# 02_GAP9_CHIP_POWER.net
KiCad netlist of a schematic drawn in Altium Designer
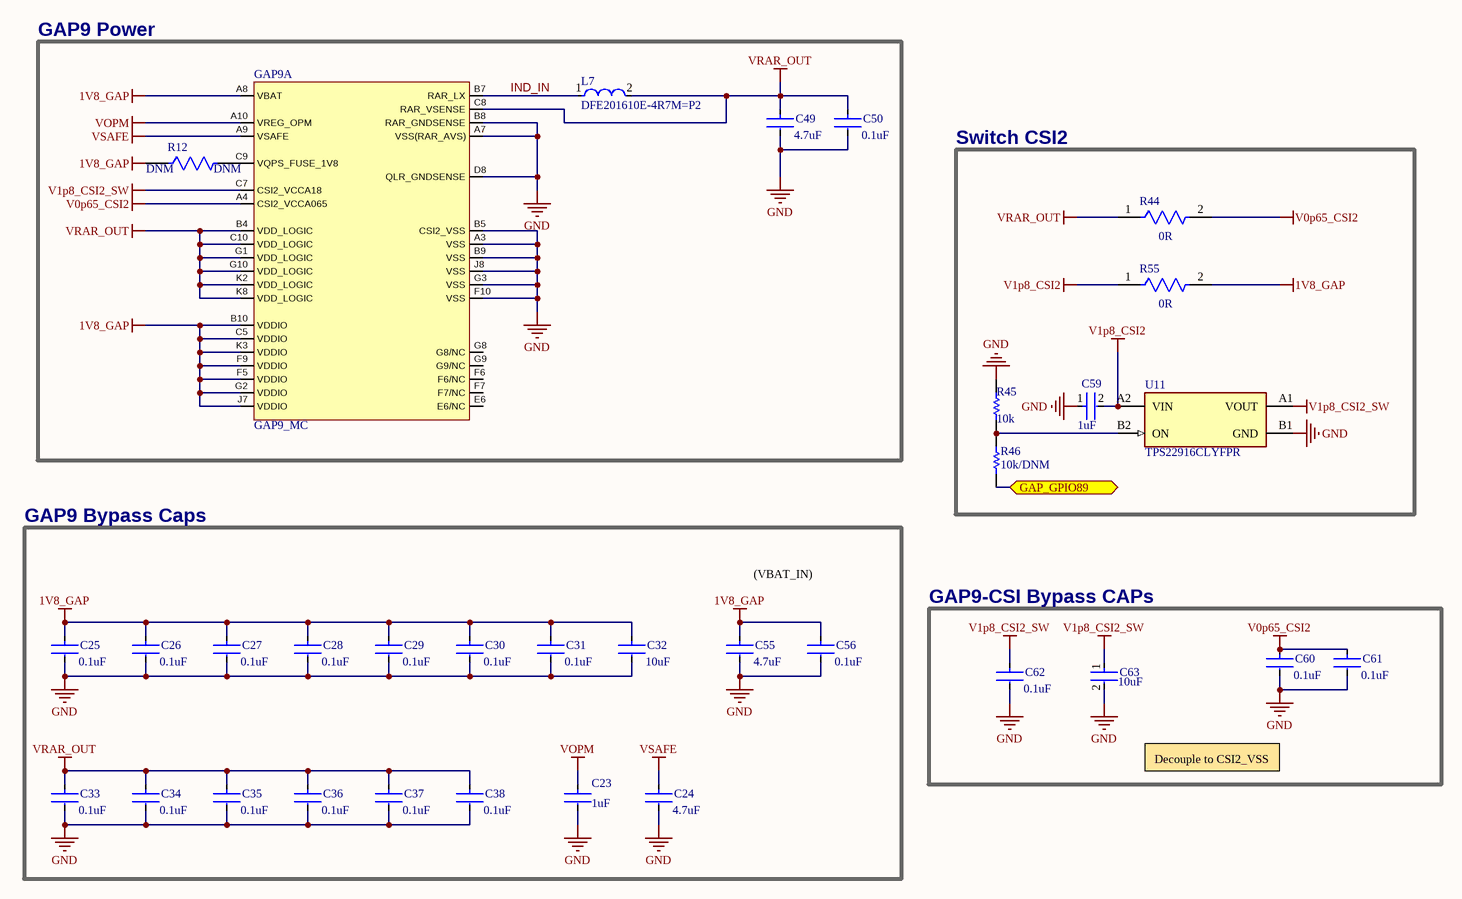
[diagram p0: 02_GAP9_CHIP_POWER.SchDoc]

(export (version "E")
  (design (tool "Eeschema 10.0.6"))
  (components
    (comp (ref "C23")
      (value "CL03A105KP3NSNC")
      (footprint "FP-CL03-IPC_B")
      (description "Cap Ceramic 1uF 10V X5R ±10% Pad SMD 0201 +85°C T/R")
      (fields (field (name "TOLERANCE") "10%") (field (name "CAPACITANCE") "1uF"))
      (libsource (lib "Altium Content Vault") (part "b4654b650e69147ec39a6b967a45e02"))
    )
    (comp (ref "C24")
      (value "C1005X5R0J475K050BC")
      (footprint "FP-C1005-050-0_15-IPC_B")
      (description "Chip Multilayer Ceramic Capacitors for General Purpose, 0402, 4.7uF")
      (fields
        (field (name "VOLTAGE") "6.3V")
        (field (name "CAPACITANCE") "4.7uF")
        (field (name "TOLERANCE") "10%")
      )
      (libsource (lib "Altium Content Vault") (part "02cd4be3c70576c341d710602a673aa"))
    )
    (comp (ref "C25")
      (value "GRM033Z71C104KE14D")
      (footprint "FP-GRM033-0_03-IPC_B")
      (description "Chip Multilayer Ceramic Capacitors for General Purpose, 0201, 0.10uF, X7R, 15%, 10%, 16V")
      (fields (field (name "CAPACITANCE") "0.1uF"))
      (libsource (lib "Altium Content Vault") (part "b4654b650e69147ec39a6b967a45e02"))
    )
    (comp (ref "C26")
      (value "GRM033Z71C104KE14D")
      (footprint "FP-GRM033-0_03-IPC_B")
      (description "Chip Multilayer Ceramic Capacitors for General Purpose, 0201, 0.10uF, X7R, 15%, 10%, 16V")
      (fields (field (name "CAPACITANCE") "0.1uF"))
      (libsource (lib "Altium Content Vault") (part "b4654b650e69147ec39a6b967a45e02"))
    )
    (comp (ref "C27")
      (value "GRM033Z71C104KE14D")
      (footprint "FP-GRM033-0_03-IPC_B")
      (description "Chip Multilayer Ceramic Capacitors for General Purpose, 0201, 0.10uF, X7R, 15%, 10%, 16V")
      (fields (field (name "CAPACITANCE") "0.1uF"))
      (libsource (lib "Altium Content Vault") (part "b4654b650e69147ec39a6b967a45e02"))
    )
    (comp (ref "C28")
      (value "GRM033Z71C104KE14D")
      (footprint "FP-GRM033-0_03-IPC_B")
      (description "Chip Multilayer Ceramic Capacitors for General Purpose, 0201, 0.10uF, X7R, 15%, 10%, 16V")
      (fields (field (name "CAPACITANCE") "0.1uF"))
      (libsource (lib "Altium Content Vault") (part "b4654b650e69147ec39a6b967a45e02"))
    )
    (comp (ref "C29")
      (value "GRM033Z71C104KE14D")
      (footprint "FP-GRM033-0_03-IPC_B")
      (description "Chip Multilayer Ceramic Capacitors for General Purpose, 0201, 0.10uF, X7R, 15%, 10%, 16V")
      (fields (field (name "CAPACITANCE") "0.1uF"))
      (libsource (lib "Altium Content Vault") (part "b4654b650e69147ec39a6b967a45e02"))
    )
    (comp (ref "C30")
      (value "GRM033Z71C104KE14D")
      (footprint "FP-GRM033-0_03-IPC_B")
      (description "Chip Multilayer Ceramic Capacitors for General Purpose, 0201, 0.10uF, X7R, 15%, 10%, 16V")
      (fields (field (name "CAPACITANCE") "0.1uF"))
      (libsource (lib "Altium Content Vault") (part "b4654b650e69147ec39a6b967a45e02"))
    )
    (comp (ref "C31")
      (value "GRM033Z71C104KE14D")
      (footprint "FP-GRM033-0_03-IPC_B")
      (description "Chip Multilayer Ceramic Capacitors for General Purpose, 0201, 0.10uF, X7R, 15%, 10%, 16V")
      (fields (field (name "CAPACITANCE") "0.1uF"))
      (libsource (lib "Altium Content Vault") (part "b4654b650e69147ec39a6b967a45e02"))
    )
    (comp (ref "C32")
      (value "CL05A106MP5NUNC")
      (footprint "FP-CL05A106MP5NUNC-IPC_B")
      (description "CAP CER 10UF 10V X5R 0402")
      (fields
        (field (name "OCTOPART") "https://octopart.com/cl05a106mp5nunc-samsung-22457395")
        (field (name "TOLERANCE") "20%")
        (field (name "CAPACITANCE") "10uF")
      )
      (libsource (lib "Altium Content Vault") (part "b4654b650e69147ec39a6b967a45e02"))
    )
    (comp (ref "C33")
      (value "GRM033Z71C104KE14D")
      (footprint "FP-GRM033-0_03-IPC_B")
      (description "Chip Multilayer Ceramic Capacitors for General Purpose, 0201, 0.10uF, X7R, 15%, 10%, 16V")
      (fields (field (name "CAPACITANCE") "0.1uF"))
      (libsource (lib "Altium Content Vault") (part "b4654b650e69147ec39a6b967a45e02"))
    )
    (comp (ref "C34")
      (value "GRM033Z71C104KE14D")
      (footprint "FP-GRM033-0_03-IPC_B")
      (description "Chip Multilayer Ceramic Capacitors for General Purpose, 0201, 0.10uF, X7R, 15%, 10%, 16V")
      (fields (field (name "CAPACITANCE") "0.1uF"))
      (libsource (lib "Altium Content Vault") (part "b4654b650e69147ec39a6b967a45e02"))
    )
    (comp (ref "C35")
      (value "GRM033Z71C104KE14D")
      (footprint "FP-GRM033-0_03-IPC_B")
      (description "Chip Multilayer Ceramic Capacitors for General Purpose, 0201, 0.10uF, X7R, 15%, 10%, 16V")
      (fields (field (name "CAPACITANCE") "0.1uF"))
      (libsource (lib "Altium Content Vault") (part "b4654b650e69147ec39a6b967a45e02"))
    )
    (comp (ref "C36")
      (value "GRM033Z71C104KE14D")
      (footprint "FP-GRM033-0_03-IPC_B")
      (description "Chip Multilayer Ceramic Capacitors for General Purpose, 0201, 0.10uF, X7R, 15%, 10%, 16V")
      (fields (field (name "CAPACITANCE") "0.1uF"))
      (libsource (lib "Altium Content Vault") (part "b4654b650e69147ec39a6b967a45e02"))
    )
    (comp (ref "C37")
      (value "GRM033Z71C104KE14D")
      (footprint "FP-GRM033-0_03-IPC_B")
      (description "Chip Multilayer Ceramic Capacitors for General Purpose, 0201, 0.10uF, X7R, 15%, 10%, 16V")
      (fields (field (name "CAPACITANCE") "0.1uF"))
      (libsource (lib "Altium Content Vault") (part "b4654b650e69147ec39a6b967a45e02"))
    )
    (comp (ref "C38")
      (value "GRM033Z71C104KE14D")
      (footprint "FP-GRM033-0_03-IPC_B")
      (description "Chip Multilayer Ceramic Capacitors for General Purpose, 0201, 0.10uF, X7R, 15%, 10%, 16V")
      (fields (field (name "CAPACITANCE") "0.1uF"))
      (libsource (lib "Altium Content Vault") (part "b4654b650e69147ec39a6b967a45e02"))
    )
    (comp (ref "C49")
      (value "C1005X5R0J475K050BC")
      (footprint "FP-C1005-050-0_15-IPC_B")
      (description "Chip Multilayer Ceramic Capacitors for General Purpose, 0402, 4.7uF")
      (fields
        (field (name "VOLTAGE") "6.3V")
        (field (name "CAPACITANCE") "4.7uF")
        (field (name "TOLERANCE") "10%")
      )
      (libsource (lib "Altium Content Vault") (part "02cd4be3c70576c341d710602a673aa"))
    )
    (comp (ref "C50")
      (value "GRM033Z71C104KE14D")
      (footprint "FP-GRM033-0_03-IPC_B")
      (description "Chip Multilayer Ceramic Capacitors for General Purpose, 0201, 0.10uF, X7R, 15%, 10%, 16V")
      (fields (field (name "CAPACITANCE") "0.1uF"))
      (libsource (lib "Altium Content Vault") (part "b4654b650e69147ec39a6b967a45e02"))
    )
    (comp (ref "C55")
      (value "C1005X5R0J475K050BC")
      (footprint "FP-C1005-050-0_15-IPC_B")
      (description "Chip Multilayer Ceramic Capacitors for General Purpose, 0402, 4.7uF")
      (fields
        (field (name "VOLTAGE") "6.3V")
        (field (name "CAPACITANCE") "4.7uF")
        (field (name "TOLERANCE") "10%")
      )
      (libsource (lib "Altium Content Vault") (part "02cd4be3c70576c341d710602a673aa"))
    )
    (comp (ref "C56")
      (value "GRM033Z71C104KE14D")
      (footprint "FP-GRM033-0_03-IPC_B")
      (description "Chip Multilayer Ceramic Capacitors for General Purpose, 0201, 0.10uF, X7R, 15%, 10%, 16V")
      (fields (field (name "CAPACITANCE") "0.1uF"))
      (libsource (lib "Altium Content Vault") (part "b4654b650e69147ec39a6b967a45e02"))
    )
    (comp (ref "C59")
      (value "1uF")
      (footprint "FP-GRM033-0_09-IPC_C")
      (description "Chip Multilayer Ceramic Capacitors for General Purpose, 0201, 1.0uF, X6S, 22%, 20%, 10V")
      (fields (field (name "TOLERANCE") "20%") (field (name "Comment") "GRM033C81A105ME05D"))
      (libsource (lib "") (part "02cd4be3c70576c341d710602a673aa_1"))
    )
    (comp (ref "C60")
      (value "GRM033Z71C104KE14D")
      (footprint "FP-GRM033-0_03-IPC_B")
      (description "Chip Multilayer Ceramic Capacitors for General Purpose, 0201, 0.10uF, X7R, 15%, 10%, 16V")
      (fields (field (name "CAPACITANCE") "0.1uF"))
      (libsource (lib "Altium Content Vault") (part "b4654b650e69147ec39a6b967a45e02"))
    )
    (comp (ref "C61")
      (value "GRM033Z71C104KE14D")
      (footprint "FP-GRM033-0_03-IPC_B")
      (description "Chip Multilayer Ceramic Capacitors for General Purpose, 0201, 0.10uF, X7R, 15%, 10%, 16V")
      (fields (field (name "CAPACITANCE") "0.1uF"))
      (libsource (lib "Altium Content Vault") (part "b4654b650e69147ec39a6b967a45e02"))
    )
    (comp (ref "C62")
      (value "GRM033Z71C104KE14D")
      (footprint "FP-GRM033-0_03-IPC_B")
      (description "Chip Multilayer Ceramic Capacitors for General Purpose, 0201, 0.10uF, X7R, 15%, 10%, 16V")
      (fields (field (name "CAPACITANCE") "0.1uF"))
      (libsource (lib "Altium Content Vault") (part "b4654b650e69147ec39a6b967a45e02"))
    )
    (comp (ref "C63")
      (value "10uF")
      (footprint "FP-CL05A106MP5NUNC-MFG")
      (description "CAP CER 10UF 10V X5R 0402")
      (fields
        (field (name "OCTOPART") "https://octopart.com/cl05a106mp5nunc-samsung-22457395")
        (field (name "TOLERANCE") "20%")
      )
      (libsource (lib "") (part "b4654b650e69147ec39a6b967a45e02_1"))
    )
    (comp (ref "GAP9") (value "GAP9_MC") (footprint "GAP9") (libsource (lib "EEG_SchLib") (part "GAP9_MC")))
    (comp (ref "L7")
      (value "DFE201610E-4R7M=P2")
      (footprint "FP-DFE201610C-MFG")
      (description "Shielded Wirewound Inductor 4.7uH 20% 1100mA 0.288Ω 0806 (2016)")
      (libsource (lib "Altium Content Vault") (part "725321dda6339637d4d059423bc1c3c"))
    )
    (comp (ref "R12")
      (value "DNM")
      (footprint "0402")
      (description "Resistor")
      (fields (field (name "ALTIUM_VALUE") "DNM"))
      (libsource (lib "EEG_SchLib") (part "RES DNM 0402"))
    )
    (comp (ref "R44")
      (value "0R")
      (footprint "FP-CRCW0402-C-e3-MFG")
      (description "RES 0 OHM JUMPER 1/16W 0402")
      (fields (field (name "Comment") "CRCW04020000Z0EDC"))
      (libsource (lib "Altium Content Vault") (part "1029c3af85768c4190bb7ad29bc67b5"))
    )
    (comp (ref "R45")
      (value "10k")
      (footprint "RESC0603X28X15LL05T05")
      (fields (field (name "MANUFACTURER") "Vishay Dale") (field (name "PART NUMBER") "CRCW020110K0FNED"))
      (libsource (lib "Altium Content Vault") (part "RES"))
    )
    (comp (ref "R46")
      (value "10k/DNM")
      (footprint "RESC0603X28X15LL05T05")
      (fields (field (name "MANUFACTURER") "Vishay Dale") (field (name "PART NUMBER") "CRCW020110K0FNED"))
      (libsource (lib "Altium Content Vault") (part "RES"))
    )
    (comp (ref "R55")
      (value "0R")
      (footprint "FP-CRCW0402-C-e3-MFG")
      (description "RES 0 OHM JUMPER 1/16W 0402")
      (fields (field (name "Comment") "CRCW04020000Z0EDC"))
      (libsource (lib "Altium Content Vault") (part "1029c3af85768c4190bb7ad29bc67b5"))
    )
    (comp (ref "U11")
      (value "TPS22916CLYFPR")
      (footprint "FP-YFP0004-IPC_C")
      (description "IC PWR SWITCH P-CHAN 1:1 4DSBGA")
      (libsource (lib "Altium Content Vault") (part "704fe9c5689264e682a31c308a68c4c"))
    )
  )
  (nets
    (net (code "1") (name "/GAP_GPIO89") (class "Default")
      (node (ref "R46") (pin "2") (pinfunction "2_2") (pintype "passive"))
    )
    (net (code "2") (name "/IND_IN") (class "Default")
      (node (ref "GAP9") (pin "B7") (pinfunction "RAR_LX_B7") (pintype "passive"))
      (node (ref "L7") (pin "1") (pinfunction "1_1") (pintype "passive"))
    )
    (net (code "3") (name "1V8_GAP") (class "Default")
      (node (ref "C25") (pin "1") (pinfunction "1_1") (pintype "passive"))
      (node (ref "C26") (pin "1") (pinfunction "1_1") (pintype "passive"))
      (node (ref "C27") (pin "1") (pinfunction "1_1") (pintype "passive"))
      (node (ref "C28") (pin "1") (pinfunction "1_1") (pintype "passive"))
      (node (ref "C29") (pin "1") (pinfunction "1_1") (pintype "passive"))
      (node (ref "C30") (pin "1") (pinfunction "1_1") (pintype "passive"))
      (node (ref "C31") (pin "1") (pinfunction "1_1") (pintype "passive"))
      (node (ref "C32") (pin "1") (pinfunction "1_1") (pintype "passive"))
      (node (ref "C55") (pin "1") (pinfunction "1_1") (pintype "passive"))
      (node (ref "C56") (pin "1") (pinfunction "1_1") (pintype "passive"))
      (node (ref "GAP9") (pin "A8") (pinfunction "VBAT_A8") (pintype "passive"))
      (node (ref "GAP9") (pin "B10") (pinfunction "VDDIO_B10") (pintype "passive"))
      (node (ref "GAP9") (pin "C5") (pinfunction "VDDIO_C5") (pintype "passive"))
      (node (ref "GAP9") (pin "F5") (pinfunction "VDDIO_F5") (pintype "passive"))
      (node (ref "GAP9") (pin "F9") (pinfunction "VDDIO_F9") (pintype "passive"))
      (node (ref "GAP9") (pin "G2") (pinfunction "VDDIO_G2") (pintype "passive"))
      (node (ref "GAP9") (pin "J7") (pinfunction "VDDIO_J7") (pintype "passive"))
      (node (ref "GAP9") (pin "K3") (pinfunction "VDDIO_K3") (pintype "passive"))
      (node (ref "R12") (pin "1") (pinfunction "1_1") (pintype "passive"))
      (node (ref "R55") (pin "2") (pinfunction "2_2") (pintype "passive"))
    )
    (net (code "4") (name "GND") (class "Default")
      (node (ref "C23") (pin "2") (pinfunction "2_2") (pintype "passive"))
      (node (ref "C24") (pin "2") (pinfunction "2_2") (pintype "passive"))
      (node (ref "C25") (pin "2") (pinfunction "2_2") (pintype "passive"))
      (node (ref "C26") (pin "2") (pinfunction "2_2") (pintype "passive"))
      (node (ref "C27") (pin "2") (pinfunction "2_2") (pintype "passive"))
      (node (ref "C28") (pin "2") (pinfunction "2_2") (pintype "passive"))
      (node (ref "C29") (pin "2") (pinfunction "2_2") (pintype "passive"))
      (node (ref "C30") (pin "2") (pinfunction "2_2") (pintype "passive"))
      (node (ref "C31") (pin "2") (pinfunction "2_2") (pintype "passive"))
      (node (ref "C32") (pin "2") (pinfunction "2_2") (pintype "passive"))
      (node (ref "C33") (pin "2") (pinfunction "2_2") (pintype "passive"))
      (node (ref "C34") (pin "2") (pinfunction "2_2") (pintype "passive"))
      (node (ref "C35") (pin "2") (pinfunction "2_2") (pintype "passive"))
      (node (ref "C36") (pin "2") (pinfunction "2_2") (pintype "passive"))
      (node (ref "C37") (pin "2") (pinfunction "2_2") (pintype "passive"))
      (node (ref "C38") (pin "2") (pinfunction "2_2") (pintype "passive"))
      (node (ref "C49") (pin "2") (pinfunction "2_2") (pintype "passive"))
      (node (ref "C50") (pin "2") (pinfunction "2_2") (pintype "passive"))
      (node (ref "C55") (pin "2") (pinfunction "2_2") (pintype "passive"))
      (node (ref "C56") (pin "2") (pinfunction "2_2") (pintype "passive"))
      (node (ref "C59") (pin "1") (pinfunction "1_1") (pintype "passive"))
      (node (ref "C60") (pin "2") (pinfunction "2_2") (pintype "passive"))
      (node (ref "C61") (pin "2") (pinfunction "2_2") (pintype "passive"))
      (node (ref "C62") (pin "2") (pinfunction "2_2") (pintype "passive"))
      (node (ref "C63") (pin "2") (pinfunction "2_2") (pintype "passive"))
      (node (ref "GAP9") (pin "A3") (pinfunction "VSS_A3") (pintype "passive"))
      (node (ref "GAP9") (pin "A7") (pinfunction "VSS(RAR_AVS)_A7") (pintype "passive"))
      (node (ref "GAP9") (pin "B5") (pinfunction "CSI2_VSS_B5") (pintype "passive"))
      (node (ref "GAP9") (pin "B8") (pinfunction "RAR_GNDSENSE_B8") (pintype "passive"))
      (node (ref "GAP9") (pin "B9") (pinfunction "VSS_B9") (pintype "passive"))
      (node (ref "GAP9") (pin "D8") (pinfunction "QLR_GNDSENSE_D8") (pintype "passive"))
      (node (ref "GAP9") (pin "F10") (pinfunction "VSS_F10") (pintype "passive"))
      (node (ref "GAP9") (pin "G3") (pinfunction "VSS_G3") (pintype "passive"))
      (node (ref "GAP9") (pin "J8") (pinfunction "VSS_J8") (pintype "passive"))
      (node (ref "R45") (pin "2") (pinfunction "2_2") (pintype "passive"))
      (node (ref "U11") (pin "B1") (pinfunction "GND_B1") (pintype "power_in"))
    )
    (net (code "5") (name "Net-(GAP9A-VQPS_FUSE_1V8)") (class "Default")
      (node (ref "GAP9") (pin "C9") (pinfunction "VQPS_FUSE_1V8_C9") (pintype "passive"))
      (node (ref "R12") (pin "2") (pinfunction "2_2") (pintype "passive"))
    )
    (net (code "6") (name "Net-(U11-ON)") (class "Default")
      (node (ref "R45") (pin "1") (pinfunction "1_1") (pintype "passive"))
      (node (ref "R46") (pin "1") (pinfunction "1_1") (pintype "passive"))
      (node (ref "U11") (pin "B2") (pinfunction "ON_B2") (pintype "input"))
    )
    (net (code "7") (name "V0p65_CSI2") (class "Default")
      (node (ref "C60") (pin "1") (pinfunction "1_1") (pintype "passive"))
      (node (ref "C61") (pin "1") (pinfunction "1_1") (pintype "passive"))
      (node (ref "GAP9") (pin "A4") (pinfunction "CSI2_VCCA065_A4") (pintype "passive"))
      (node (ref "R44") (pin "2") (pinfunction "2_2") (pintype "passive"))
    )
    (net (code "8") (name "V1p8_CSI2") (class "Default")
      (node (ref "C59") (pin "2") (pinfunction "2_2") (pintype "passive"))
      (node (ref "R55") (pin "1") (pinfunction "1_1") (pintype "passive"))
      (node (ref "U11") (pin "A2") (pinfunction "VIN_A2") (pintype "power_in"))
    )
    (net (code "9") (name "V1p8_CSI2_SW") (class "Default")
      (node (ref "C62") (pin "1") (pinfunction "1_1") (pintype "passive"))
      (node (ref "C63") (pin "1") (pinfunction "1_1") (pintype "passive"))
      (node (ref "GAP9") (pin "C7") (pinfunction "CSI2_VCCA18_C7") (pintype "passive"))
      (node (ref "U11") (pin "A1") (pinfunction "VOUT_A1") (pintype "power_in"))
    )
    (net (code "10") (name "VOPM") (class "Default")
      (node (ref "C23") (pin "1") (pinfunction "1_1") (pintype "passive"))
      (node (ref "GAP9") (pin "A10") (pinfunction "VREG_OPM_A10") (pintype "passive"))
    )
    (net (code "11") (name "VRAR_OUT") (class "Default")
      (node (ref "C33") (pin "1") (pinfunction "1_1") (pintype "passive"))
      (node (ref "C34") (pin "1") (pinfunction "1_1") (pintype "passive"))
      (node (ref "C35") (pin "1") (pinfunction "1_1") (pintype "passive"))
      (node (ref "C36") (pin "1") (pinfunction "1_1") (pintype "passive"))
      (node (ref "C37") (pin "1") (pinfunction "1_1") (pintype "passive"))
      (node (ref "C38") (pin "1") (pinfunction "1_1") (pintype "passive"))
      (node (ref "C49") (pin "1") (pinfunction "1_1") (pintype "passive"))
      (node (ref "C50") (pin "1") (pinfunction "1_1") (pintype "passive"))
      (node (ref "GAP9") (pin "B4") (pinfunction "VDD_LOGIC_B4") (pintype "passive"))
      (node (ref "GAP9") (pin "C10") (pinfunction "VDD_LOGIC_C10") (pintype "passive"))
      (node (ref "GAP9") (pin "C8") (pinfunction "RAR_VSENSE_C8") (pintype "passive"))
      (node (ref "GAP9") (pin "G1") (pinfunction "VDD_LOGIC_G1") (pintype "passive"))
      (node (ref "GAP9") (pin "G10") (pinfunction "VDD_LOGIC_G10") (pintype "passive"))
      (node (ref "GAP9") (pin "K2") (pinfunction "VDD_LOGIC_K2") (pintype "passive"))
      (node (ref "GAP9") (pin "K8") (pinfunction "VDD_LOGIC_K8") (pintype "passive"))
      (node (ref "L7") (pin "2") (pinfunction "2_2") (pintype "passive"))
      (node (ref "R44") (pin "1") (pinfunction "1_1") (pintype "passive"))
    )
    (net (code "12") (name "VSAFE") (class "Default")
      (node (ref "C24") (pin "1") (pinfunction "1_1") (pintype "passive"))
      (node (ref "GAP9") (pin "A9") (pinfunction "VSAFE_A9") (pintype "passive"))
    )
    (net (code "13") (name "unconnected-(GAP9A-E6{slash}NC-PadE6)") (class "Default")
      (node (ref "GAP9") (pin "E6") (pinfunction "E6/NC_E6") (pintype "passive"))
    )
    (net (code "14") (name "unconnected-(GAP9A-F6{slash}NC-PadF6)") (class "Default")
      (node (ref "GAP9") (pin "F6") (pinfunction "F6/NC_F6") (pintype "passive"))
    )
    (net (code "15") (name "unconnected-(GAP9A-F7{slash}NC-PadF7)") (class "Default")
      (node (ref "GAP9") (pin "F7") (pinfunction "F7/NC_F7") (pintype "passive"))
    )
    (net (code "16") (name "unconnected-(GAP9A-G8{slash}NC-PadG8)") (class "Default")
      (node (ref "GAP9") (pin "G8") (pinfunction "G8/NC_G8") (pintype "passive"))
    )
    (net (code "17") (name "unconnected-(GAP9A-G9{slash}NC-PadG9)") (class "Default")
      (node (ref "GAP9") (pin "G9") (pinfunction "G9/NC_G9") (pintype "passive"))
    )
  )
)
